# KeyInput.net
KiCad netlist of a schematic drawn in Altium Designer
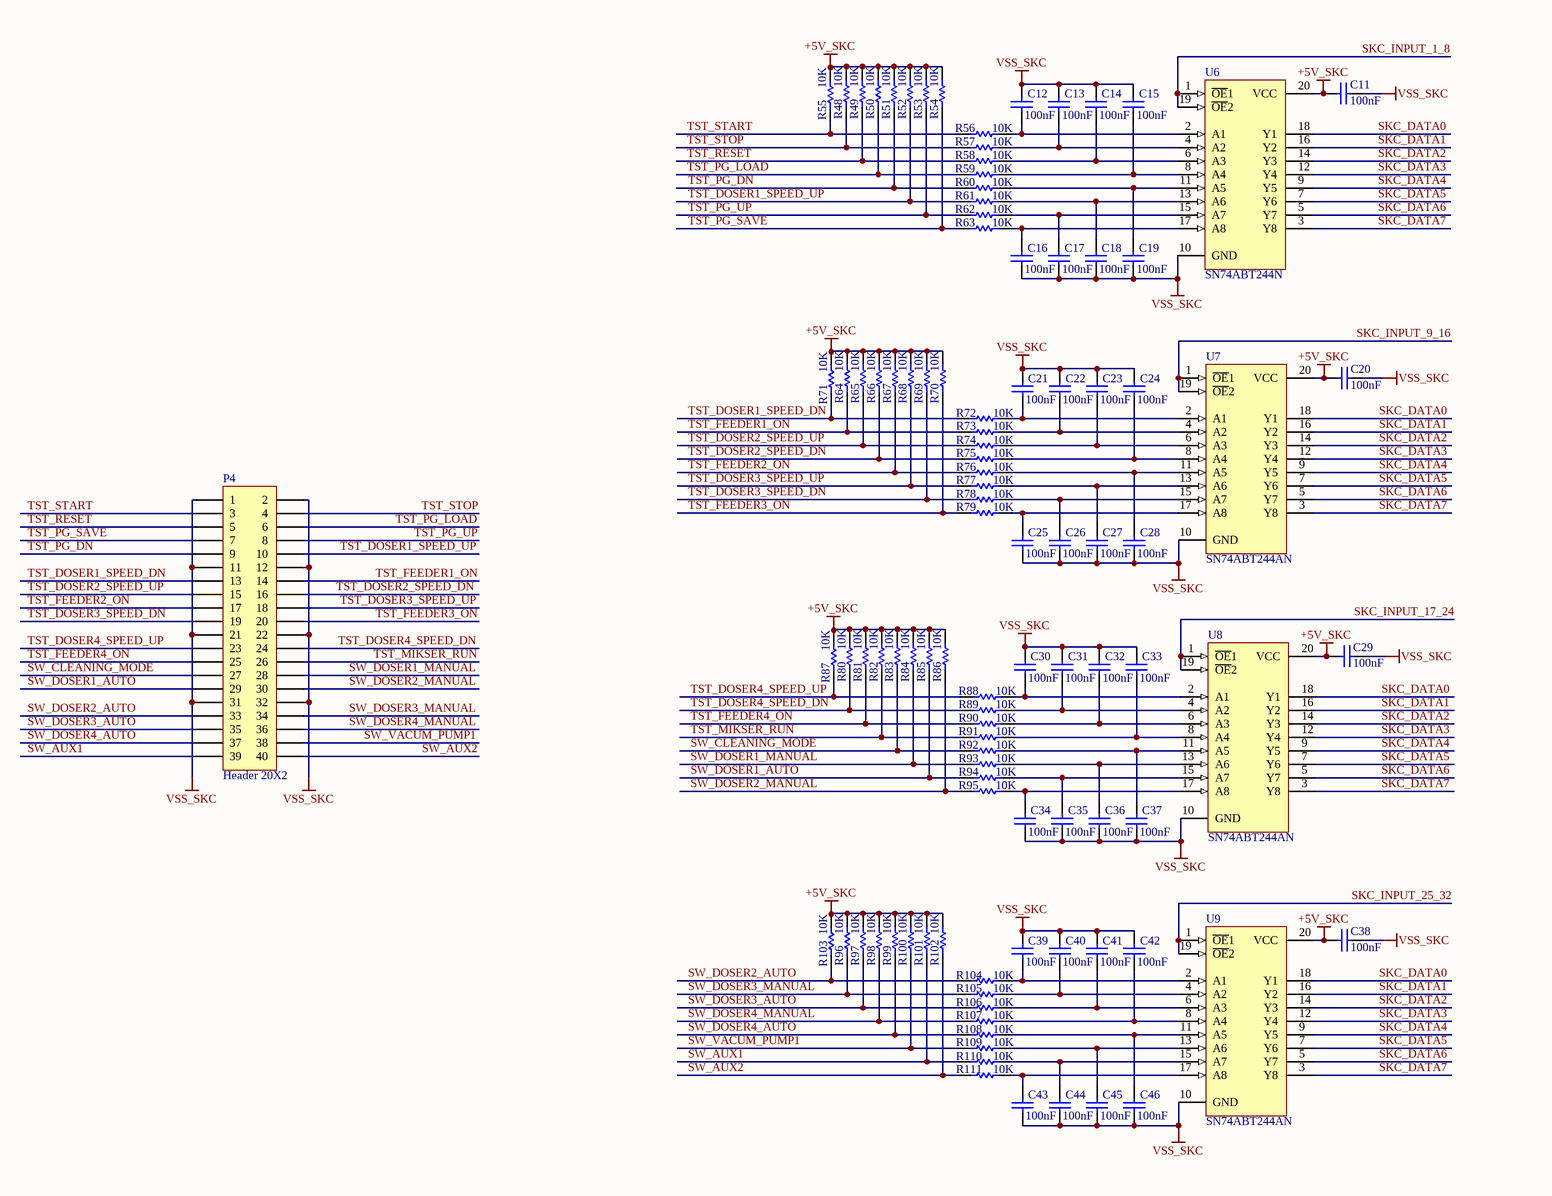
[diagram p0: KeyInput.SchDoc]

(export (version "E")
  (design (tool "Eeschema 10.0.6"))
  (components
    (comp (ref "C11")
      (value "100nF")
      (footprint "1206")
      (description "Ceramic Chip Capacitor - Standard")
      (fields (field (name "PUBLISHER") "Altium Limited"))
      (libsource (lib "KEMET Chip Capacitor") (part "C1206"))
    )
    (comp (ref "C12")
      (value "100nF")
      (footprint "1206")
      (description "Ceramic Chip Capacitor - Standard")
      (fields (field (name "PUBLISHER") "Altium Limited"))
      (libsource (lib "KEMET Chip Capacitor") (part "C1206"))
    )
    (comp (ref "C13")
      (value "100nF")
      (footprint "1206")
      (description "Ceramic Chip Capacitor - Standard")
      (fields (field (name "PUBLISHER") "Altium Limited"))
      (libsource (lib "KEMET Chip Capacitor") (part "C1206"))
    )
    (comp (ref "C14")
      (value "100nF")
      (footprint "1206")
      (description "Ceramic Chip Capacitor - Standard")
      (fields (field (name "PUBLISHER") "Altium Limited"))
      (libsource (lib "KEMET Chip Capacitor") (part "C1206"))
    )
    (comp (ref "C15")
      (value "100nF")
      (footprint "1206")
      (description "Ceramic Chip Capacitor - Standard")
      (fields (field (name "PUBLISHER") "Altium Limited"))
      (libsource (lib "KEMET Chip Capacitor") (part "C1206"))
    )
    (comp (ref "C16")
      (value "100nF")
      (footprint "1206")
      (description "Ceramic Chip Capacitor - Standard")
      (fields (field (name "PUBLISHER") "Altium Limited"))
      (libsource (lib "KEMET Chip Capacitor") (part "C1206"))
    )
    (comp (ref "C17")
      (value "100nF")
      (footprint "1206")
      (description "Ceramic Chip Capacitor - Standard")
      (fields (field (name "PUBLISHER") "Altium Limited"))
      (libsource (lib "KEMET Chip Capacitor") (part "C1206"))
    )
    (comp (ref "C18")
      (value "100nF")
      (footprint "1206")
      (description "Ceramic Chip Capacitor - Standard")
      (fields (field (name "PUBLISHER") "Altium Limited"))
      (libsource (lib "KEMET Chip Capacitor") (part "C1206"))
    )
    (comp (ref "C19")
      (value "100nF")
      (footprint "1206")
      (description "Ceramic Chip Capacitor - Standard")
      (fields (field (name "PUBLISHER") "Altium Limited"))
      (libsource (lib "KEMET Chip Capacitor") (part "C1206"))
    )
    (comp (ref "C20")
      (value "100nF")
      (footprint "1206")
      (description "Ceramic Chip Capacitor - Standard")
      (fields (field (name "PUBLISHER") "Altium Limited"))
      (libsource (lib "KEMET Chip Capacitor") (part "C1206"))
    )
    (comp (ref "C21")
      (value "100nF")
      (footprint "1206")
      (description "Ceramic Chip Capacitor - Standard")
      (fields (field (name "PUBLISHER") "Altium Limited"))
      (libsource (lib "KEMET Chip Capacitor") (part "C1206"))
    )
    (comp (ref "C22")
      (value "100nF")
      (footprint "1206")
      (description "Ceramic Chip Capacitor - Standard")
      (fields (field (name "PUBLISHER") "Altium Limited"))
      (libsource (lib "KEMET Chip Capacitor") (part "C1206"))
    )
    (comp (ref "C23")
      (value "100nF")
      (footprint "1206")
      (description "Ceramic Chip Capacitor - Standard")
      (fields (field (name "PUBLISHER") "Altium Limited"))
      (libsource (lib "KEMET Chip Capacitor") (part "C1206"))
    )
    (comp (ref "C24")
      (value "100nF")
      (footprint "1206")
      (description "Ceramic Chip Capacitor - Standard")
      (fields (field (name "PUBLISHER") "Altium Limited"))
      (libsource (lib "KEMET Chip Capacitor") (part "C1206"))
    )
    (comp (ref "C25")
      (value "100nF")
      (footprint "1206")
      (description "Ceramic Chip Capacitor - Standard")
      (fields (field (name "PUBLISHER") "Altium Limited"))
      (libsource (lib "KEMET Chip Capacitor") (part "C1206"))
    )
    (comp (ref "C26")
      (value "100nF")
      (footprint "1206")
      (description "Ceramic Chip Capacitor - Standard")
      (fields (field (name "PUBLISHER") "Altium Limited"))
      (libsource (lib "KEMET Chip Capacitor") (part "C1206"))
    )
    (comp (ref "C27")
      (value "100nF")
      (footprint "1206")
      (description "Ceramic Chip Capacitor - Standard")
      (fields (field (name "PUBLISHER") "Altium Limited"))
      (libsource (lib "KEMET Chip Capacitor") (part "C1206"))
    )
    (comp (ref "C28")
      (value "100nF")
      (footprint "1206")
      (description "Ceramic Chip Capacitor - Standard")
      (fields (field (name "PUBLISHER") "Altium Limited"))
      (libsource (lib "KEMET Chip Capacitor") (part "C1206"))
    )
    (comp (ref "C29")
      (value "100nF")
      (footprint "1206")
      (description "Ceramic Chip Capacitor - Standard")
      (fields (field (name "PUBLISHER") "Altium Limited"))
      (libsource (lib "KEMET Chip Capacitor") (part "C1206"))
    )
    (comp (ref "C30")
      (value "100nF")
      (footprint "1206")
      (description "Ceramic Chip Capacitor - Standard")
      (fields (field (name "PUBLISHER") "Altium Limited"))
      (libsource (lib "KEMET Chip Capacitor") (part "C1206"))
    )
    (comp (ref "C31")
      (value "100nF")
      (footprint "1206")
      (description "Ceramic Chip Capacitor - Standard")
      (fields (field (name "PUBLISHER") "Altium Limited"))
      (libsource (lib "KEMET Chip Capacitor") (part "C1206"))
    )
    (comp (ref "C32")
      (value "100nF")
      (footprint "1206")
      (description "Ceramic Chip Capacitor - Standard")
      (fields (field (name "PUBLISHER") "Altium Limited"))
      (libsource (lib "KEMET Chip Capacitor") (part "C1206"))
    )
    (comp (ref "C33")
      (value "100nF")
      (footprint "1206")
      (description "Ceramic Chip Capacitor - Standard")
      (fields (field (name "PUBLISHER") "Altium Limited"))
      (libsource (lib "KEMET Chip Capacitor") (part "C1206"))
    )
    (comp (ref "C34")
      (value "100nF")
      (footprint "1206")
      (description "Ceramic Chip Capacitor - Standard")
      (fields (field (name "PUBLISHER") "Altium Limited"))
      (libsource (lib "KEMET Chip Capacitor") (part "C1206"))
    )
    (comp (ref "C35")
      (value "100nF")
      (footprint "1206")
      (description "Ceramic Chip Capacitor - Standard")
      (fields (field (name "PUBLISHER") "Altium Limited"))
      (libsource (lib "KEMET Chip Capacitor") (part "C1206"))
    )
    (comp (ref "C36")
      (value "100nF")
      (footprint "1206")
      (description "Ceramic Chip Capacitor - Standard")
      (fields (field (name "PUBLISHER") "Altium Limited"))
      (libsource (lib "KEMET Chip Capacitor") (part "C1206"))
    )
    (comp (ref "C37")
      (value "100nF")
      (footprint "1206")
      (description "Ceramic Chip Capacitor - Standard")
      (fields (field (name "PUBLISHER") "Altium Limited"))
      (libsource (lib "KEMET Chip Capacitor") (part "C1206"))
    )
    (comp (ref "C38")
      (value "100nF")
      (footprint "1206")
      (description "Ceramic Chip Capacitor - Standard")
      (fields (field (name "PUBLISHER") "Altium Limited"))
      (libsource (lib "KEMET Chip Capacitor") (part "C1206"))
    )
    (comp (ref "C39")
      (value "100nF")
      (footprint "1206")
      (description "Ceramic Chip Capacitor - Standard")
      (fields (field (name "PUBLISHER") "Altium Limited"))
      (libsource (lib "KEMET Chip Capacitor") (part "C1206"))
    )
    (comp (ref "C40")
      (value "100nF")
      (footprint "1206")
      (description "Ceramic Chip Capacitor - Standard")
      (fields (field (name "PUBLISHER") "Altium Limited"))
      (libsource (lib "KEMET Chip Capacitor") (part "C1206"))
    )
    (comp (ref "C41")
      (value "100nF")
      (footprint "1206")
      (description "Ceramic Chip Capacitor - Standard")
      (fields (field (name "PUBLISHER") "Altium Limited"))
      (libsource (lib "KEMET Chip Capacitor") (part "C1206"))
    )
    (comp (ref "C42")
      (value "100nF")
      (footprint "1206")
      (description "Ceramic Chip Capacitor - Standard")
      (fields (field (name "PUBLISHER") "Altium Limited"))
      (libsource (lib "KEMET Chip Capacitor") (part "C1206"))
    )
    (comp (ref "C43")
      (value "100nF")
      (footprint "1206")
      (description "Ceramic Chip Capacitor - Standard")
      (fields (field (name "PUBLISHER") "Altium Limited"))
      (libsource (lib "KEMET Chip Capacitor") (part "C1206"))
    )
    (comp (ref "C44")
      (value "100nF")
      (footprint "1206")
      (description "Ceramic Chip Capacitor - Standard")
      (fields (field (name "PUBLISHER") "Altium Limited"))
      (libsource (lib "KEMET Chip Capacitor") (part "C1206"))
    )
    (comp (ref "C45")
      (value "100nF")
      (footprint "1206")
      (description "Ceramic Chip Capacitor - Standard")
      (fields (field (name "PUBLISHER") "Altium Limited"))
      (libsource (lib "KEMET Chip Capacitor") (part "C1206"))
    )
    (comp (ref "C46")
      (value "100nF")
      (footprint "1206")
      (description "Ceramic Chip Capacitor - Standard")
      (fields (field (name "PUBLISHER") "Altium Limited"))
      (libsource (lib "KEMET Chip Capacitor") (part "C1206"))
    )
    (comp (ref "P4")
      (value "Header 20X2")
      (footprint "HDR2X20")
      (description "Header, 20-Pin, Dual row")
      (fields (field (name "PUBLISHER") "Altium Limited"))
      (libsource (lib "Miscellaneous Connectors") (part "Header 20X2"))
    )
    (comp (ref "R48")
      (value "10K")
      (footprint "ERA-0805")
      (fields (field (name "PUBLISHER") "Altium Limited"))
      (libsource (lib "Panasonic Resistor") (part "ERA6Y"))
    )
    (comp (ref "R49")
      (value "10K")
      (footprint "ERA-0805")
      (fields (field (name "PUBLISHER") "Altium Limited"))
      (libsource (lib "Panasonic Resistor") (part "ERA6Y"))
    )
    (comp (ref "R50")
      (value "10K")
      (footprint "ERA-0805")
      (fields (field (name "PUBLISHER") "Altium Limited"))
      (libsource (lib "Panasonic Resistor") (part "ERA6Y"))
    )
    (comp (ref "R51")
      (value "10K")
      (footprint "ERA-0805")
      (fields (field (name "PUBLISHER") "Altium Limited"))
      (libsource (lib "Panasonic Resistor") (part "ERA6Y"))
    )
    (comp (ref "R52")
      (value "10K")
      (footprint "ERA-0805")
      (fields (field (name "PUBLISHER") "Altium Limited"))
      (libsource (lib "Panasonic Resistor") (part "ERA6Y"))
    )
    (comp (ref "R53")
      (value "10K")
      (footprint "ERA-0805")
      (fields (field (name "PUBLISHER") "Altium Limited"))
      (libsource (lib "Panasonic Resistor") (part "ERA6Y"))
    )
    (comp (ref "R54")
      (value "10K")
      (footprint "ERA-0805")
      (fields (field (name "PUBLISHER") "Altium Limited"))
      (libsource (lib "Panasonic Resistor") (part "ERA6Y"))
    )
    (comp (ref "R55")
      (value "10K")
      (footprint "ERA-0805")
      (fields (field (name "PUBLISHER") "Altium Limited"))
      (libsource (lib "Panasonic Resistor") (part "ERA6Y"))
    )
    (comp (ref "R56")
      (value "10K")
      (footprint "ERA-0805")
      (fields (field (name "PUBLISHER") "Altium Limited"))
      (libsource (lib "Panasonic Resistor") (part "ERA6Y"))
    )
    (comp (ref "R57")
      (value "10K")
      (footprint "ERA-0805")
      (fields (field (name "PUBLISHER") "Altium Limited"))
      (libsource (lib "Panasonic Resistor") (part "ERA6Y"))
    )
    (comp (ref "R58")
      (value "10K")
      (footprint "ERA-0805")
      (fields (field (name "PUBLISHER") "Altium Limited"))
      (libsource (lib "Panasonic Resistor") (part "ERA6Y"))
    )
    (comp (ref "R59")
      (value "10K")
      (footprint "ERA-0805")
      (fields (field (name "PUBLISHER") "Altium Limited"))
      (libsource (lib "Panasonic Resistor") (part "ERA6Y"))
    )
    (comp (ref "R60")
      (value "10K")
      (footprint "ERA-0805")
      (fields (field (name "PUBLISHER") "Altium Limited"))
      (libsource (lib "Panasonic Resistor") (part "ERA6Y"))
    )
    (comp (ref "R61")
      (value "10K")
      (footprint "ERA-0805")
      (fields (field (name "PUBLISHER") "Altium Limited"))
      (libsource (lib "Panasonic Resistor") (part "ERA6Y"))
    )
    (comp (ref "R62")
      (value "10K")
      (footprint "ERA-0805")
      (fields (field (name "PUBLISHER") "Altium Limited"))
      (libsource (lib "Panasonic Resistor") (part "ERA6Y"))
    )
    (comp (ref "R63")
      (value "10K")
      (footprint "ERA-0805")
      (fields (field (name "PUBLISHER") "Altium Limited"))
      (libsource (lib "Panasonic Resistor") (part "ERA6Y"))
    )
    (comp (ref "R64")
      (value "10K")
      (footprint "ERA-0805")
      (fields (field (name "PUBLISHER") "Altium Limited"))
      (libsource (lib "Panasonic Resistor") (part "ERA6Y"))
    )
    (comp (ref "R65")
      (value "10K")
      (footprint "ERA-0805")
      (fields (field (name "PUBLISHER") "Altium Limited"))
      (libsource (lib "Panasonic Resistor") (part "ERA6Y"))
    )
    (comp (ref "R66")
      (value "10K")
      (footprint "ERA-0805")
      (fields (field (name "PUBLISHER") "Altium Limited"))
      (libsource (lib "Panasonic Resistor") (part "ERA6Y"))
    )
    (comp (ref "R67")
      (value "10K")
      (footprint "ERA-0805")
      (fields (field (name "PUBLISHER") "Altium Limited"))
      (libsource (lib "Panasonic Resistor") (part "ERA6Y"))
    )
    (comp (ref "R68")
      (value "10K")
      (footprint "ERA-0805")
      (fields (field (name "PUBLISHER") "Altium Limited"))
      (libsource (lib "Panasonic Resistor") (part "ERA6Y"))
    )
    (comp (ref "R69")
      (value "10K")
      (footprint "ERA-0805")
      (fields (field (name "PUBLISHER") "Altium Limited"))
      (libsource (lib "Panasonic Resistor") (part "ERA6Y"))
    )
    (comp (ref "R70")
      (value "10K")
      (footprint "ERA-0805")
      (fields (field (name "PUBLISHER") "Altium Limited"))
      (libsource (lib "Panasonic Resistor") (part "ERA6Y"))
    )
    (comp (ref "R71")
      (value "10K")
      (footprint "ERA-0805")
      (fields (field (name "PUBLISHER") "Altium Limited"))
      (libsource (lib "Panasonic Resistor") (part "ERA6Y"))
    )
    (comp (ref "R72")
      (value "10K")
      (footprint "ERA-0805")
      (fields (field (name "PUBLISHER") "Altium Limited"))
      (libsource (lib "Panasonic Resistor") (part "ERA6Y"))
    )
    (comp (ref "R73")
      (value "10K")
      (footprint "ERA-0805")
      (fields (field (name "PUBLISHER") "Altium Limited"))
      (libsource (lib "Panasonic Resistor") (part "ERA6Y"))
    )
    (comp (ref "R74")
      (value "10K")
      (footprint "ERA-0805")
      (fields (field (name "PUBLISHER") "Altium Limited"))
      (libsource (lib "Panasonic Resistor") (part "ERA6Y"))
    )
    (comp (ref "R75")
      (value "10K")
      (footprint "ERA-0805")
      (fields (field (name "PUBLISHER") "Altium Limited"))
      (libsource (lib "Panasonic Resistor") (part "ERA6Y"))
    )
    (comp (ref "R76")
      (value "10K")
      (footprint "ERA-0805")
      (fields (field (name "PUBLISHER") "Altium Limited"))
      (libsource (lib "Panasonic Resistor") (part "ERA6Y"))
    )
    (comp (ref "R77")
      (value "10K")
      (footprint "ERA-0805")
      (fields (field (name "PUBLISHER") "Altium Limited"))
      (libsource (lib "Panasonic Resistor") (part "ERA6Y"))
    )
    (comp (ref "R78")
      (value "10K")
      (footprint "ERA-0805")
      (fields (field (name "PUBLISHER") "Altium Limited"))
      (libsource (lib "Panasonic Resistor") (part "ERA6Y"))
    )
    (comp (ref "R79")
      (value "10K")
      (footprint "ERA-0805")
      (fields (field (name "PUBLISHER") "Altium Limited"))
      (libsource (lib "Panasonic Resistor") (part "ERA6Y"))
    )
    (comp (ref "R80")
      (value "10K")
      (footprint "ERA-0805")
      (fields (field (name "PUBLISHER") "Altium Limited"))
      (libsource (lib "Panasonic Resistor") (part "ERA6Y"))
    )
    (comp (ref "R81")
      (value "10K")
      (footprint "ERA-0805")
      (fields (field (name "PUBLISHER") "Altium Limited"))
      (libsource (lib "Panasonic Resistor") (part "ERA6Y"))
    )
    (comp (ref "R82")
      (value "10K")
      (footprint "ERA-0805")
      (fields (field (name "PUBLISHER") "Altium Limited"))
      (libsource (lib "Panasonic Resistor") (part "ERA6Y"))
    )
    (comp (ref "R83")
      (value "10K")
      (footprint "ERA-0805")
      (fields (field (name "PUBLISHER") "Altium Limited"))
      (libsource (lib "Panasonic Resistor") (part "ERA6Y"))
    )
    (comp (ref "R84")
      (value "10K")
      (footprint "ERA-0805")
      (fields (field (name "PUBLISHER") "Altium Limited"))
      (libsource (lib "Panasonic Resistor") (part "ERA6Y"))
    )
    (comp (ref "R85")
      (value "10K")
      (footprint "ERA-0805")
      (fields (field (name "PUBLISHER") "Altium Limited"))
      (libsource (lib "Panasonic Resistor") (part "ERA6Y"))
    )
    (comp (ref "R86")
      (value "10K")
      (footprint "ERA-0805")
      (fields (field (name "PUBLISHER") "Altium Limited"))
      (libsource (lib "Panasonic Resistor") (part "ERA6Y"))
    )
    (comp (ref "R87")
      (value "10K")
      (footprint "ERA-0805")
      (fields (field (name "PUBLISHER") "Altium Limited"))
      (libsource (lib "Panasonic Resistor") (part "ERA6Y"))
    )
    (comp (ref "R88")
      (value "10K")
      (footprint "ERA-0805")
      (fields (field (name "PUBLISHER") "Altium Limited"))
      (libsource (lib "Panasonic Resistor") (part "ERA6Y"))
    )
    (comp (ref "R89")
      (value "10K")
      (footprint "ERA-0805")
      (fields (field (name "PUBLISHER") "Altium Limited"))
      (libsource (lib "Panasonic Resistor") (part "ERA6Y"))
    )
    (comp (ref "R90")
      (value "10K")
      (footprint "ERA-0805")
      (fields (field (name "PUBLISHER") "Altium Limited"))
      (libsource (lib "Panasonic Resistor") (part "ERA6Y"))
    )
    (comp (ref "R91")
      (value "10K")
      (footprint "ERA-0805")
      (fields (field (name "PUBLISHER") "Altium Limited"))
      (libsource (lib "Panasonic Resistor") (part "ERA6Y"))
    )
    (comp (ref "R92")
      (value "10K")
      (footprint "ERA-0805")
      (fields (field (name "PUBLISHER") "Altium Limited"))
      (libsource (lib "Panasonic Resistor") (part "ERA6Y"))
    )
    (comp (ref "R93")
      (value "10K")
      (footprint "ERA-0805")
      (fields (field (name "PUBLISHER") "Altium Limited"))
      (libsource (lib "Panasonic Resistor") (part "ERA6Y"))
    )
    (comp (ref "R94")
      (value "10K")
      (footprint "ERA-0805")
      (fields (field (name "PUBLISHER") "Altium Limited"))
      (libsource (lib "Panasonic Resistor") (part "ERA6Y"))
    )
    (comp (ref "R95")
      (value "10K")
      (footprint "ERA-0805")
      (fields (field (name "PUBLISHER") "Altium Limited"))
      (libsource (lib "Panasonic Resistor") (part "ERA6Y"))
    )
    (comp (ref "R96")
      (value "10K")
      (footprint "ERA-0805")
      (fields (field (name "PUBLISHER") "Altium Limited"))
      (libsource (lib "Panasonic Resistor") (part "ERA6Y"))
    )
    (comp (ref "R97")
      (value "10K")
      (footprint "ERA-0805")
      (fields (field (name "PUBLISHER") "Altium Limited"))
      (libsource (lib "Panasonic Resistor") (part "ERA6Y"))
    )
    (comp (ref "R98")
      (value "10K")
      (footprint "ERA-0805")
      (fields (field (name "PUBLISHER") "Altium Limited"))
      (libsource (lib "Panasonic Resistor") (part "ERA6Y"))
    )
    (comp (ref "R99")
      (value "10K")
      (footprint "ERA-0805")
      (fields (field (name "PUBLISHER") "Altium Limited"))
      (libsource (lib "Panasonic Resistor") (part "ERA6Y"))
    )
    (comp (ref "R100")
      (value "10K")
      (footprint "ERA-0805")
      (fields (field (name "PUBLISHER") "Altium Limited"))
      (libsource (lib "Panasonic Resistor") (part "ERA6Y"))
    )
    (comp (ref "R101")
      (value "10K")
      (footprint "ERA-0805")
      (fields (field (name "PUBLISHER") "Altium Limited"))
      (libsource (lib "Panasonic Resistor") (part "ERA6Y"))
    )
    (comp (ref "R102")
      (value "10K")
      (footprint "ERA-0805")
      (fields (field (name "PUBLISHER") "Altium Limited"))
      (libsource (lib "Panasonic Resistor") (part "ERA6Y"))
    )
    (comp (ref "R103")
      (value "10K")
      (footprint "ERA-0805")
      (fields (field (name "PUBLISHER") "Altium Limited"))
      (libsource (lib "Panasonic Resistor") (part "ERA6Y"))
    )
    (comp (ref "R104")
      (value "10K")
      (footprint "ERA-0805")
      (fields (field (name "PUBLISHER") "Altium Limited"))
      (libsource (lib "Panasonic Resistor") (part "ERA6Y"))
    )
    (comp (ref "R105")
      (value "10K")
      (footprint "ERA-0805")
      (fields (field (name "PUBLISHER") "Altium Limited"))
      (libsource (lib "Panasonic Resistor") (part "ERA6Y"))
    )
    (comp (ref "R106")
      (value "10K")
      (footprint "ERA-0805")
      (fields (field (name "PUBLISHER") "Altium Limited"))
      (libsource (lib "Panasonic Resistor") (part "ERA6Y"))
    )
    (comp (ref "R107")
      (value "10K")
      (footprint "ERA-0805")
      (fields (field (name "PUBLISHER") "Altium Limited"))
      (libsource (lib "Panasonic Resistor") (part "ERA6Y"))
    )
    (comp (ref "R108")
      (value "10K")
      (footprint "ERA-0805")
      (fields (field (name "PUBLISHER") "Altium Limited"))
      (libsource (lib "Panasonic Resistor") (part "ERA6Y"))
    )
    (comp (ref "R109")
      (value "10K")
      (footprint "ERA-0805")
      (fields (field (name "PUBLISHER") "Altium Limited"))
      (libsource (lib "Panasonic Resistor") (part "ERA6Y"))
    )
    (comp (ref "R110")
      (value "10K")
      (footprint "ERA-0805")
      (fields (field (name "PUBLISHER") "Altium Limited"))
      (libsource (lib "Panasonic Resistor") (part "ERA6Y"))
    )
    (comp (ref "R111")
      (value "10K")
      (footprint "ERA-0805")
      (fields (field (name "PUBLISHER") "Altium Limited"))
      (libsource (lib "Panasonic Resistor") (part "ERA6Y"))
    )
    (comp (ref "U6")
      (value "SN74ABT244N")
      (footprint "N020")
      (description "Octal Buffer/Driver with 3-State Outputs")
      (fields (field (name "PUBLISHER") "Altium Limited"))
      (libsource (lib "TI Logic Buffer Line Driver") (part "SN74ABT244N"))
    )
    (comp (ref "U7")
      (value "SN74ABT244AN")
      (footprint "N020")
      (description "Octal Buffer/Driver with 3-State Outputs")
      (fields (field (name "PUBLISHER") "Altium Limited"))
      (libsource (lib "TI Logic Buffer Line Driver") (part "SN74ABT244AN"))
    )
    (comp (ref "U8")
      (value "SN74ABT244AN")
      (footprint "N020")
      (description "Octal Buffer/Driver with 3-State Outputs")
      (fields (field (name "PUBLISHER") "Altium Limited"))
      (libsource (lib "TI Logic Buffer Line Driver") (part "SN74ABT244AN"))
    )
    (comp (ref "U9")
      (value "SN74ABT244AN")
      (footprint "N020")
      (description "Octal Buffer/Driver with 3-State Outputs")
      (fields (field (name "PUBLISHER") "Altium Limited"))
      (libsource (lib "TI Logic Buffer Line Driver") (part "SN74ABT244AN"))
    )
  )
  (nets
    (net (code "1") (name "+5V_SKC") (class "Default")
      (node (ref "C11") (pin "1") (pinfunction "1_1") (pintype "passive"))
      (node (ref "C20") (pin "1") (pinfunction "1_1") (pintype "passive"))
      (node (ref "C29") (pin "1") (pinfunction "1_1") (pintype "passive"))
      (node (ref "C38") (pin "1") (pinfunction "1_1") (pintype "passive"))
      (node (ref "R100") (pin "2") (pinfunction "2_2") (pintype "passive"))
      (node (ref "R101") (pin "2") (pinfunction "2_2") (pintype "passive"))
      (node (ref "R102") (pin "2") (pinfunction "2_2") (pintype "passive"))
      (node (ref "R103") (pin "2") (pinfunction "2_2") (pintype "passive"))
      (node (ref "R48") (pin "2") (pinfunction "2_2") (pintype "passive"))
      (node (ref "R49") (pin "2") (pinfunction "2_2") (pintype "passive"))
      (node (ref "R50") (pin "2") (pinfunction "2_2") (pintype "passive"))
      (node (ref "R51") (pin "2") (pinfunction "2_2") (pintype "passive"))
      (node (ref "R52") (pin "2") (pinfunction "2_2") (pintype "passive"))
      (node (ref "R53") (pin "2") (pinfunction "2_2") (pintype "passive"))
      (node (ref "R54") (pin "2") (pinfunction "2_2") (pintype "passive"))
      (node (ref "R55") (pin "2") (pinfunction "2_2") (pintype "passive"))
      (node (ref "R64") (pin "2") (pinfunction "2_2") (pintype "passive"))
      (node (ref "R65") (pin "2") (pinfunction "2_2") (pintype "passive"))
      (node (ref "R66") (pin "2") (pinfunction "2_2") (pintype "passive"))
      (node (ref "R67") (pin "2") (pinfunction "2_2") (pintype "passive"))
      (node (ref "R68") (pin "2") (pinfunction "2_2") (pintype "passive"))
      (node (ref "R69") (pin "2") (pinfunction "2_2") (pintype "passive"))
      (node (ref "R70") (pin "2") (pinfunction "2_2") (pintype "passive"))
      (node (ref "R71") (pin "2") (pinfunction "2_2") (pintype "passive"))
      (node (ref "R80") (pin "2") (pinfunction "2_2") (pintype "passive"))
      (node (ref "R81") (pin "2") (pinfunction "2_2") (pintype "passive"))
      (node (ref "R82") (pin "2") (pinfunction "2_2") (pintype "passive"))
      (node (ref "R83") (pin "2") (pinfunction "2_2") (pintype "passive"))
      (node (ref "R84") (pin "2") (pinfunction "2_2") (pintype "passive"))
      (node (ref "R85") (pin "2") (pinfunction "2_2") (pintype "passive"))
      (node (ref "R86") (pin "2") (pinfunction "2_2") (pintype "passive"))
      (node (ref "R87") (pin "2") (pinfunction "2_2") (pintype "passive"))
      (node (ref "R96") (pin "2") (pinfunction "2_2") (pintype "passive"))
      (node (ref "R97") (pin "2") (pinfunction "2_2") (pintype "passive"))
      (node (ref "R98") (pin "2") (pinfunction "2_2") (pintype "passive"))
      (node (ref "R99") (pin "2") (pinfunction "2_2") (pintype "passive"))
      (node (ref "U6") (pin "20") (pinfunction "VCC_20") (pintype "power_in"))
      (node (ref "U7") (pin "20") (pinfunction "VCC_20") (pintype "power_in"))
      (node (ref "U8") (pin "20") (pinfunction "VCC_20") (pintype "power_in"))
      (node (ref "U9") (pin "20") (pinfunction "VCC_20") (pintype "power_in"))
    )
    (net (code "2") (name "/SKC_DATA0") (class "Default")
      (node (ref "U6") (pin "18") (pinfunction "Y1_18") (pintype "tri_state"))
      (node (ref "U7") (pin "18") (pinfunction "Y1_18") (pintype "tri_state"))
      (node (ref "U8") (pin "18") (pinfunction "Y1_18") (pintype "tri_state"))
      (node (ref "U9") (pin "18") (pinfunction "Y1_18") (pintype "tri_state"))
    )
    (net (code "3") (name "/SKC_DATA1") (class "Default")
      (node (ref "U6") (pin "16") (pinfunction "Y2_16") (pintype "tri_state"))
      (node (ref "U7") (pin "16") (pinfunction "Y2_16") (pintype "tri_state"))
      (node (ref "U8") (pin "16") (pinfunction "Y2_16") (pintype "tri_state"))
      (node (ref "U9") (pin "16") (pinfunction "Y2_16") (pintype "tri_state"))
    )
    (net (code "4") (name "/SKC_DATA2") (class "Default")
      (node (ref "U6") (pin "14") (pinfunction "Y3_14") (pintype "tri_state"))
      (node (ref "U7") (pin "14") (pinfunction "Y3_14") (pintype "tri_state"))
      (node (ref "U8") (pin "14") (pinfunction "Y3_14") (pintype "tri_state"))
      (node (ref "U9") (pin "14") (pinfunction "Y3_14") (pintype "tri_state"))
    )
    (net (code "5") (name "/SKC_DATA3") (class "Default")
      (node (ref "U6") (pin "12") (pinfunction "Y4_12") (pintype "tri_state"))
      (node (ref "U7") (pin "12") (pinfunction "Y4_12") (pintype "tri_state"))
      (node (ref "U8") (pin "12") (pinfunction "Y4_12") (pintype "tri_state"))
      (node (ref "U9") (pin "12") (pinfunction "Y4_12") (pintype "tri_state"))
    )
    (net (code "6") (name "/SKC_DATA4") (class "Default")
      (node (ref "U6") (pin "9") (pinfunction "Y5_9") (pintype "tri_state"))
      (node (ref "U7") (pin "9") (pinfunction "Y5_9") (pintype "tri_state"))
      (node (ref "U8") (pin "9") (pinfunction "Y5_9") (pintype "tri_state"))
      (node (ref "U9") (pin "9") (pinfunction "Y5_9") (pintype "tri_state"))
    )
    (net (code "7") (name "/SKC_DATA5") (class "Default")
      (node (ref "U6") (pin "7") (pinfunction "Y6_7") (pintype "tri_state"))
      (node (ref "U7") (pin "7") (pinfunction "Y6_7") (pintype "tri_state"))
      (node (ref "U8") (pin "7") (pinfunction "Y6_7") (pintype "tri_state"))
      (node (ref "U9") (pin "7") (pinfunction "Y6_7") (pintype "tri_state"))
    )
    (net (code "8") (name "/SKC_DATA6") (class "Default")
      (node (ref "U6") (pin "5") (pinfunction "Y7_5") (pintype "tri_state"))
      (node (ref "U7") (pin "5") (pinfunction "Y7_5") (pintype "tri_state"))
      (node (ref "U8") (pin "5") (pinfunction "Y7_5") (pintype "tri_state"))
      (node (ref "U9") (pin "5") (pinfunction "Y7_5") (pintype "tri_state"))
    )
    (net (code "9") (name "/SKC_DATA7") (class "Default")
      (node (ref "U6") (pin "3") (pinfunction "Y8_3") (pintype "tri_state"))
      (node (ref "U7") (pin "3") (pinfunction "Y8_3") (pintype "tri_state"))
      (node (ref "U8") (pin "3") (pinfunction "Y8_3") (pintype "tri_state"))
      (node (ref "U9") (pin "3") (pinfunction "Y8_3") (pintype "tri_state"))
    )
    (net (code "10") (name "/SKC_INPUT_1_8") (class "Default")
      (node (ref "U6") (pin "1") (pinfunction "~{OE}1_1") (pintype "input"))
      (node (ref "U6") (pin "19") (pinfunction "~{OE}2_19") (pintype "input"))
    )
    (net (code "11") (name "/SKC_INPUT_9_16") (class "Default")
      (node (ref "U7") (pin "1") (pinfunction "~{OE}1_1") (pintype "input"))
      (node (ref "U7") (pin "19") (pinfunction "~{OE}2_19") (pintype "input"))
    )
    (net (code "12") (name "/SKC_INPUT_17_24") (class "Default")
      (node (ref "U8") (pin "1") (pinfunction "~{OE}1_1") (pintype "input"))
      (node (ref "U8") (pin "19") (pinfunction "~{OE}2_19") (pintype "input"))
    )
    (net (code "13") (name "/SKC_INPUT_25_32") (class "Default")
      (node (ref "U9") (pin "1") (pinfunction "~{OE}1_1") (pintype "input"))
      (node (ref "U9") (pin "19") (pinfunction "~{OE}2_19") (pintype "input"))
    )
    (net (code "14") (name "/SW_AUX1") (class "Default")
      (node (ref "P4") (pin "39") (pinfunction "39_39") (pintype "passive"))
      (node (ref "R101") (pin "1") (pinfunction "1_1") (pintype "passive"))
      (node (ref "R110") (pin "1") (pinfunction "1_1") (pintype "passive"))
    )
    (net (code "15") (name "/SW_AUX2") (class "Default")
      (node (ref "P4") (pin "40") (pinfunction "40_40") (pintype "passive"))
      (node (ref "R102") (pin "1") (pinfunction "1_1") (pintype "passive"))
      (node (ref "R111") (pin "1") (pinfunction "1_1") (pintype "passive"))
    )
    (net (code "16") (name "/SW_CLEANING_MODE") (class "Default")
      (node (ref "P4") (pin "27") (pinfunction "27_27") (pintype "passive"))
      (node (ref "R83") (pin "1") (pinfunction "1_1") (pintype "passive"))
      (node (ref "R92") (pin "1") (pinfunction "1_1") (pintype "passive"))
    )
    (net (code "17") (name "/SW_DOSER1_AUTO") (class "Default")
      (node (ref "P4") (pin "29") (pinfunction "29_29") (pintype "passive"))
      (node (ref "R85") (pin "1") (pinfunction "1_1") (pintype "passive"))
      (node (ref "R94") (pin "1") (pinfunction "1_1") (pintype "passive"))
    )
    (net (code "18") (name "/SW_DOSER1_MANUAL") (class "Default")
      (node (ref "P4") (pin "28") (pinfunction "28_28") (pintype "passive"))
      (node (ref "R84") (pin "1") (pinfunction "1_1") (pintype "passive"))
      (node (ref "R93") (pin "1") (pinfunction "1_1") (pintype "passive"))
    )
    (net (code "19") (name "/SW_DOSER2_AUTO") (class "Default")
      (node (ref "P4") (pin "33") (pinfunction "33_33") (pintype "passive"))
      (node (ref "R103") (pin "1") (pinfunction "1_1") (pintype "passive"))
      (node (ref "R104") (pin "1") (pinfunction "1_1") (pintype "passive"))
    )
    (net (code "20") (name "/SW_DOSER2_MANUAL") (class "Default")
      (node (ref "P4") (pin "30") (pinfunction "30_30") (pintype "passive"))
      (node (ref "R86") (pin "1") (pinfunction "1_1") (pintype "passive"))
      (node (ref "R95") (pin "1") (pinfunction "1_1") (pintype "passive"))
    )
    (net (code "21") (name "/SW_DOSER3_AUTO") (class "Default")
      (node (ref "P4") (pin "35") (pinfunction "35_35") (pintype "passive"))
      (node (ref "R106") (pin "1") (pinfunction "1_1") (pintype "passive"))
      (node (ref "R97") (pin "1") (pinfunction "1_1") (pintype "passive"))
    )
    (net (code "22") (name "/SW_DOSER3_MANUAL") (class "Default")
      (node (ref "P4") (pin "34") (pinfunction "34_34") (pintype "passive"))
      (node (ref "R105") (pin "1") (pinfunction "1_1") (pintype "passive"))
      (node (ref "R96") (pin "1") (pinfunction "1_1") (pintype "passive"))
    )
    (net (code "23") (name "/SW_DOSER4_AUTO") (class "Default")
      (node (ref "P4") (pin "37") (pinfunction "37_37") (pintype "passive"))
      (node (ref "R108") (pin "1") (pinfunction "1_1") (pintype "passive"))
      (node (ref "R99") (pin "1") (pinfunction "1_1") (pintype "passive"))
    )
    (net (code "24") (name "/SW_DOSER4_MANUAL") (class "Default")
      (node (ref "P4") (pin "36") (pinfunction "36_36") (pintype "passive"))
      (node (ref "R107") (pin "1") (pinfunction "1_1") (pintype "passive"))
      (node (ref "R98") (pin "1") (pinfunction "1_1") (pintype "passive"))
    )
    (net (code "25") (name "/SW_VACUM_PUMP1") (class "Default")
      (node (ref "P4") (pin "38") (pinfunction "38_38") (pintype "passive"))
      (node (ref "R100") (pin "1") (pinfunction "1_1") (pintype "passive"))
      (node (ref "R109") (pin "1") (pinfunction "1_1") (pintype "passive"))
    )
    (net (code "26") (name "/TST_DOSER1_SPEED_DN") (class "Default")
      (node (ref "P4") (pin "13") (pinfunction "13_13") (pintype "passive"))
      (node (ref "R71") (pin "1") (pinfunction "1_1") (pintype "passive"))
      (node (ref "R72") (pin "1") (pinfunction "1_1") (pintype "passive"))
    )
    (net (code "27") (name "/TST_DOSER1_SPEED_UP") (class "Default")
      (node (ref "P4") (pin "10") (pinfunction "10_10") (pintype "passive"))
      (node (ref "R52") (pin "1") (pinfunction "1_1") (pintype "passive"))
      (node (ref "R61") (pin "1") (pinfunction "1_1") (pintype "passive"))
    )
    (net (code "28") (name "/TST_DOSER2_SPEED_DN") (class "Default")
      (node (ref "P4") (pin "16") (pinfunction "16_16") (pintype "passive"))
      (node (ref "R66") (pin "1") (pinfunction "1_1") (pintype "passive"))
      (node (ref "R75") (pin "1") (pinfunction "1_1") (pintype "passive"))
    )
    (net (code "29") (name "/TST_DOSER2_SPEED_UP") (class "Default")
      (node (ref "P4") (pin "15") (pinfunction "15_15") (pintype "passive"))
      (node (ref "R65") (pin "1") (pinfunction "1_1") (pintype "passive"))
      (node (ref "R74") (pin "1") (pinfunction "1_1") (pintype "passive"))
    )
    (net (code "30") (name "/TST_DOSER3_SPEED_DN") (class "Default")
      (node (ref "P4") (pin "19") (pinfunction "19_19") (pintype "passive"))
      (node (ref "R69") (pin "1") (pinfunction "1_1") (pintype "passive"))
      (node (ref "R78") (pin "1") (pinfunction "1_1") (pintype "passive"))
    )
    (net (code "31") (name "/TST_DOSER3_SPEED_UP") (class "Default")
      (node (ref "P4") (pin "18") (pinfunction "18_18") (pintype "passive"))
      (node (ref "R68") (pin "1") (pinfunction "1_1") (pintype "passive"))
      (node (ref "R77") (pin "1") (pinfunction "1_1") (pintype "passive"))
    )
    (net (code "32") (name "/TST_DOSER4_SPEED_DN") (class "Default")
      (node (ref "P4") (pin "24") (pinfunction "24_24") (pintype "passive"))
      (node (ref "R80") (pin "1") (pinfunction "1_1") (pintype "passive"))
      (node (ref "R89") (pin "1") (pinfunction "1_1") (pintype "passive"))
    )
    (net (code "33") (name "/TST_DOSER4_SPEED_UP") (class "Default")
      (node (ref "P4") (pin "23") (pinfunction "23_23") (pintype "passive"))
      (node (ref "R87") (pin "1") (pinfunction "1_1") (pintype "passive"))
      (node (ref "R88") (pin "1") (pinfunction "1_1") (pintype "passive"))
    )
    (net (code "34") (name "/TST_FEEDER1_ON") (class "Default")
      (node (ref "P4") (pin "14") (pinfunction "14_14") (pintype "passive"))
      (node (ref "R64") (pin "1") (pinfunction "1_1") (pintype "passive"))
      (node (ref "R73") (pin "1") (pinfunction "1_1") (pintype "passive"))
    )
    (net (code "35") (name "/TST_FEEDER2_ON") (class "Default")
      (node (ref "P4") (pin "17") (pinfunction "17_17") (pintype "passive"))
      (node (ref "R67") (pin "1") (pinfunction "1_1") (pintype "passive"))
      (node (ref "R76") (pin "1") (pinfunction "1_1") (pintype "passive"))
    )
    (net (code "36") (name "/TST_FEEDER3_ON") (class "Default")
      (node (ref "P4") (pin "20") (pinfunction "20_20") (pintype "passive"))
      (node (ref "R70") (pin "1") (pinfunction "1_1") (pintype "passive"))
      (node (ref "R79") (pin "1") (pinfunction "1_1") (pintype "passive"))
    )
    (net (code "37") (name "/TST_FEEDER4_ON") (class "Default")
      (node (ref "P4") (pin "25") (pinfunction "25_25") (pintype "passive"))
      (node (ref "R81") (pin "1") (pinfunction "1_1") (pintype "passive"))
      (node (ref "R90") (pin "1") (pinfunction "1_1") (pintype "passive"))
    )
    (net (code "38") (name "/TST_MIKSER_RUN") (class "Default")
      (node (ref "P4") (pin "26") (pinfunction "26_26") (pintype "passive"))
      (node (ref "R82") (pin "1") (pinfunction "1_1") (pintype "passive"))
      (node (ref "R91") (pin "1") (pinfunction "1_1") (pintype "passive"))
    )
    (net (code "39") (name "/TST_PG_DN") (class "Default")
      (node (ref "P4") (pin "9") (pinfunction "9_9") (pintype "passive"))
      (node (ref "R51") (pin "1") (pinfunction "1_1") (pintype "passive"))
      (node (ref "R60") (pin "1") (pinfunction "1_1") (pintype "passive"))
    )
    (net (code "40") (name "/TST_PG_LOAD") (class "Default")
      (node (ref "P4") (pin "6") (pinfunction "6_6") (pintype "passive"))
      (node (ref "R50") (pin "1") (pinfunction "1_1") (pintype "passive"))
      (node (ref "R59") (pin "1") (pinfunction "1_1") (pintype "passive"))
    )
    (net (code "41") (name "/TST_PG_SAVE") (class "Default")
      (node (ref "P4") (pin "7") (pinfunction "7_7") (pintype "passive"))
      (node (ref "R54") (pin "1") (pinfunction "1_1") (pintype "passive"))
      (node (ref "R63") (pin "1") (pinfunction "1_1") (pintype "passive"))
    )
    (net (code "42") (name "/TST_PG_UP") (class "Default")
      (node (ref "P4") (pin "8") (pinfunction "8_8") (pintype "passive"))
      (node (ref "R53") (pin "1") (pinfunction "1_1") (pintype "passive"))
      (node (ref "R62") (pin "1") (pinfunction "1_1") (pintype "passive"))
    )
    (net (code "43") (name "/TST_RESET") (class "Default")
      (node (ref "P4") (pin "5") (pinfunction "5_5") (pintype "passive"))
      (node (ref "R49") (pin "1") (pinfunction "1_1") (pintype "passive"))
      (node (ref "R58") (pin "1") (pinfunction "1_1") (pintype "passive"))
    )
    (net (code "44") (name "/TST_START") (class "Default")
      (node (ref "P4") (pin "3") (pinfunction "3_3") (pintype "passive"))
      (node (ref "R55") (pin "1") (pinfunction "1_1") (pintype "passive"))
      (node (ref "R56") (pin "1") (pinfunction "1_1") (pintype "passive"))
    )
    (net (code "45") (name "/TST_STOP") (class "Default")
      (node (ref "P4") (pin "4") (pinfunction "4_4") (pintype "passive"))
      (node (ref "R48") (pin "1") (pinfunction "1_1") (pintype "passive"))
      (node (ref "R57") (pin "1") (pinfunction "1_1") (pintype "passive"))
    )
    (net (code "46") (name "Net-(U6-A1)") (class "Default")
      (node (ref "C12") (pin "1") (pinfunction "1_1") (pintype "passive"))
      (node (ref "R56") (pin "2") (pinfunction "2_2") (pintype "passive"))
      (node (ref "U6") (pin "2") (pinfunction "A1_2") (pintype "input"))
    )
    (net (code "47") (name "Net-(U6-A2)") (class "Default")
      (node (ref "C13") (pin "1") (pinfunction "1_1") (pintype "passive"))
      (node (ref "R57") (pin "2") (pinfunction "2_2") (pintype "passive"))
      (node (ref "U6") (pin "4") (pinfunction "A2_4") (pintype "input"))
    )
    (net (code "48") (name "Net-(U6-A3)") (class "Default")
      (node (ref "C14") (pin "1") (pinfunction "1_1") (pintype "passive"))
      (node (ref "R58") (pin "2") (pinfunction "2_2") (pintype "passive"))
      (node (ref "U6") (pin "6") (pinfunction "A3_6") (pintype "input"))
    )
    (net (code "49") (name "Net-(U6-A4)") (class "Default")
      (node (ref "C15") (pin "1") (pinfunction "1_1") (pintype "passive"))
      (node (ref "R59") (pin "2") (pinfunction "2_2") (pintype "passive"))
      (node (ref "U6") (pin "8") (pinfunction "A4_8") (pintype "input"))
    )
    (net (code "50") (name "Net-(U6-A5)") (class "Default")
      (node (ref "C19") (pin "2") (pinfunction "2_2") (pintype "passive"))
      (node (ref "R60") (pin "2") (pinfunction "2_2") (pintype "passive"))
      (node (ref "U6") (pin "11") (pinfunction "A5_11") (pintype "input"))
    )
    (net (code "51") (name "Net-(U6-A6)") (class "Default")
      (node (ref "C18") (pin "2") (pinfunction "2_2") (pintype "passive"))
      (node (ref "R61") (pin "2") (pinfunction "2_2") (pintype "passive"))
      (node (ref "U6") (pin "13") (pinfunction "A6_13") (pintype "input"))
    )
    (net (code "52") (name "Net-(U6-A7)") (class "Default")
      (node (ref "C17") (pin "2") (pinfunction "2_2") (pintype "passive"))
      (node (ref "R62") (pin "2") (pinfunction "2_2") (pintype "passive"))
      (node (ref "U6") (pin "15") (pinfunction "A7_15") (pintype "input"))
    )
    (net (code "53") (name "Net-(U6-A8)") (class "Default")
      (node (ref "C16") (pin "2") (pinfunction "2_2") (pintype "passive"))
      (node (ref "R63") (pin "2") (pinfunction "2_2") (pintype "passive"))
      (node (ref "U6") (pin "17") (pinfunction "A8_17") (pintype "input"))
    )
    (net (code "54") (name "Net-(U7-A1)") (class "Default")
      (node (ref "C21") (pin "1") (pinfunction "1_1") (pintype "passive"))
      (node (ref "R72") (pin "2") (pinfunction "2_2") (pintype "passive"))
      (node (ref "U7") (pin "2") (pinfunction "A1_2") (pintype "input"))
    )
    (net (code "55") (name "Net-(U7-A2)") (class "Default")
      (node (ref "C22") (pin "1") (pinfunction "1_1") (pintype "passive"))
      (node (ref "R73") (pin "2") (pinfunction "2_2") (pintype "passive"))
      (node (ref "U7") (pin "4") (pinfunction "A2_4") (pintype "input"))
    )
    (net (code "56") (name "Net-(U7-A3)") (class "Default")
      (node (ref "C23") (pin "1") (pinfunction "1_1") (pintype "passive"))
      (node (ref "R74") (pin "2") (pinfunction "2_2") (pintype "passive"))
      (node (ref "U7") (pin "6") (pinfunction "A3_6") (pintype "input"))
    )
    (net (code "57") (name "Net-(U7-A4)") (class "Default")
      (node (ref "C24") (pin "1") (pinfunction "1_1") (pintype "passive"))
      (node (ref "R75") (pin "2") (pinfunction "2_2") (pintype "passive"))
      (node (ref "U7") (pin "8") (pinfunction "A4_8") (pintype "input"))
    )
    (net (code "58") (name "Net-(U7-A5)") (class "Default")
      (node (ref "C28") (pin "2") (pinfunction "2_2") (pintype "passive"))
      (node (ref "R76") (pin "2") (pinfunction "2_2") (pintype "passive"))
      (node (ref "U7") (pin "11") (pinfunction "A5_11") (pintype "input"))
    )
    (net (code "59") (name "Net-(U7-A6)") (class "Default")
      (node (ref "C27") (pin "2") (pinfunction "2_2") (pintype "passive"))
      (node (ref "R77") (pin "2") (pinfunction "2_2") (pintype "passive"))
      (node (ref "U7") (pin "13") (pinfunction "A6_13") (pintype "input"))
    )
    (net (code "60") (name "Net-(U7-A7)") (class "Default")
      (node (ref "C26") (pin "2") (pinfunction "2_2") (pintype "passive"))
      (node (ref "R78") (pin "2") (pinfunction "2_2") (pintype "passive"))
      (node (ref "U7") (pin "15") (pinfunction "A7_15") (pintype "input"))
    )
    (net (code "61") (name "Net-(U7-A8)") (class "Default")
      (node (ref "C25") (pin "2") (pinfunction "2_2") (pintype "passive"))
      (node (ref "R79") (pin "2") (pinfunction "2_2") (pintype "passive"))
      (node (ref "U7") (pin "17") (pinfunction "A8_17") (pintype "input"))
    )
    (net (code "62") (name "Net-(U8-A1)") (class "Default")
      (node (ref "C30") (pin "1") (pinfunction "1_1") (pintype "passive"))
      (node (ref "R88") (pin "2") (pinfunction "2_2") (pintype "passive"))
      (node (ref "U8") (pin "2") (pinfunction "A1_2") (pintype "input"))
    )
    (net (code "63") (name "Net-(U8-A2)") (class "Default")
      (node (ref "C31") (pin "1") (pinfunction "1_1") (pintype "passive"))
      (node (ref "R89") (pin "2") (pinfunction "2_2") (pintype "passive"))
      (node (ref "U8") (pin "4") (pinfunction "A2_4") (pintype "input"))
    )
    (net (code "64") (name "Net-(U8-A3)") (class "Default")
      (node (ref "C32") (pin "1") (pinfunction "1_1") (pintype "passive"))
      (node (ref "R90") (pin "2") (pinfunction "2_2") (pintype "passive"))
      (node (ref "U8") (pin "6") (pinfunction "A3_6") (pintype "input"))
    )
    (net (code "65") (name "Net-(U8-A4)") (class "Default")
      (node (ref "C33") (pin "1") (pinfunction "1_1") (pintype "passive"))
      (node (ref "R91") (pin "2") (pinfunction "2_2") (pintype "passive"))
      (node (ref "U8") (pin "8") (pinfunction "A4_8") (pintype "input"))
    )
    (net (code "66") (name "Net-(U8-A5)") (class "Default")
      (node (ref "C37") (pin "2") (pinfunction "2_2") (pintype "passive"))
      (node (ref "R92") (pin "2") (pinfunction "2_2") (pintype "passive"))
      (node (ref "U8") (pin "11") (pinfunction "A5_11") (pintype "input"))
    )
    (net (code "67") (name "Net-(U8-A6)") (class "Default")
      (node (ref "C36") (pin "2") (pinfunction "2_2") (pintype "passive"))
      (node (ref "R93") (pin "2") (pinfunction "2_2") (pintype "passive"))
      (node (ref "U8") (pin "13") (pinfunction "A6_13") (pintype "input"))
    )
    (net (code "68") (name "Net-(U8-A7)") (class "Default")
      (node (ref "C35") (pin "2") (pinfunction "2_2") (pintype "passive"))
      (node (ref "R94") (pin "2") (pinfunction "2_2") (pintype "passive"))
      (node (ref "U8") (pin "15") (pinfunction "A7_15") (pintype "input"))
    )
    (net (code "69") (name "Net-(U8-A8)") (class "Default")
      (node (ref "C34") (pin "2") (pinfunction "2_2") (pintype "passive"))
      (node (ref "R95") (pin "2") (pinfunction "2_2") (pintype "passive"))
      (node (ref "U8") (pin "17") (pinfunction "A8_17") (pintype "input"))
    )
    (net (code "70") (name "Net-(U9-A1)") (class "Default")
      (node (ref "C39") (pin "1") (pinfunction "1_1") (pintype "passive"))
      (node (ref "R104") (pin "2") (pinfunction "2_2") (pintype "passive"))
      (node (ref "U9") (pin "2") (pinfunction "A1_2") (pintype "input"))
    )
    (net (code "71") (name "Net-(U9-A2)") (class "Default")
      (node (ref "C40") (pin "1") (pinfunction "1_1") (pintype "passive"))
      (node (ref "R105") (pin "2") (pinfunction "2_2") (pintype "passive"))
      (node (ref "U9") (pin "4") (pinfunction "A2_4") (pintype "input"))
    )
    (net (code "72") (name "Net-(U9-A3)") (class "Default")
      (node (ref "C41") (pin "1") (pinfunction "1_1") (pintype "passive"))
      (node (ref "R106") (pin "2") (pinfunction "2_2") (pintype "passive"))
      (node (ref "U9") (pin "6") (pinfunction "A3_6") (pintype "input"))
    )
    (net (code "73") (name "Net-(U9-A4)") (class "Default")
      (node (ref "C42") (pin "1") (pinfunction "1_1") (pintype "passive"))
      (node (ref "R107") (pin "2") (pinfunction "2_2") (pintype "passive"))
      (node (ref "U9") (pin "8") (pinfunction "A4_8") (pintype "input"))
    )
    (net (code "74") (name "Net-(U9-A5)") (class "Default")
      (node (ref "C46") (pin "2") (pinfunction "2_2") (pintype "passive"))
      (node (ref "R108") (pin "2") (pinfunction "2_2") (pintype "passive"))
      (node (ref "U9") (pin "11") (pinfunction "A5_11") (pintype "input"))
    )
    (net (code "75") (name "Net-(U9-A6)") (class "Default")
      (node (ref "C45") (pin "2") (pinfunction "2_2") (pintype "passive"))
      (node (ref "R109") (pin "2") (pinfunction "2_2") (pintype "passive"))
      (node (ref "U9") (pin "13") (pinfunction "A6_13") (pintype "input"))
    )
    (net (code "76") (name "Net-(U9-A7)") (class "Default")
      (node (ref "C44") (pin "2") (pinfunction "2_2") (pintype "passive"))
      (node (ref "R110") (pin "2") (pinfunction "2_2") (pintype "passive"))
      (node (ref "U9") (pin "15") (pinfunction "A7_15") (pintype "input"))
    )
    (net (code "77") (name "Net-(U9-A8)") (class "Default")
      (node (ref "C43") (pin "2") (pinfunction "2_2") (pintype "passive"))
      (node (ref "R111") (pin "2") (pinfunction "2_2") (pintype "passive"))
      (node (ref "U9") (pin "17") (pinfunction "A8_17") (pintype "input"))
    )
    (net (code "78") (name "VSS_SKC") (class "Default")
      (node (ref "C11") (pin "2") (pinfunction "2_2") (pintype "passive"))
      (node (ref "C12") (pin "2") (pinfunction "2_2") (pintype "passive"))
      (node (ref "C13") (pin "2") (pinfunction "2_2") (pintype "passive"))
      (node (ref "C14") (pin "2") (pinfunction "2_2") (pintype "passive"))
      (node (ref "C15") (pin "2") (pinfunction "2_2") (pintype "passive"))
      (node (ref "C16") (pin "1") (pinfunction "1_1") (pintype "passive"))
      (node (ref "C17") (pin "1") (pinfunction "1_1") (pintype "passive"))
      (node (ref "C18") (pin "1") (pinfunction "1_1") (pintype "passive"))
      (node (ref "C19") (pin "1") (pinfunction "1_1") (pintype "passive"))
      (node (ref "C20") (pin "2") (pinfunction "2_2") (pintype "passive"))
      (node (ref "C21") (pin "2") (pinfunction "2_2") (pintype "passive"))
      (node (ref "C22") (pin "2") (pinfunction "2_2") (pintype "passive"))
      (node (ref "C23") (pin "2") (pinfunction "2_2") (pintype "passive"))
      (node (ref "C24") (pin "2") (pinfunction "2_2") (pintype "passive"))
      (node (ref "C25") (pin "1") (pinfunction "1_1") (pintype "passive"))
      (node (ref "C26") (pin "1") (pinfunction "1_1") (pintype "passive"))
      (node (ref "C27") (pin "1") (pinfunction "1_1") (pintype "passive"))
      (node (ref "C28") (pin "1") (pinfunction "1_1") (pintype "passive"))
      (node (ref "C29") (pin "2") (pinfunction "2_2") (pintype "passive"))
      (node (ref "C30") (pin "2") (pinfunction "2_2") (pintype "passive"))
      (node (ref "C31") (pin "2") (pinfunction "2_2") (pintype "passive"))
      (node (ref "C32") (pin "2") (pinfunction "2_2") (pintype "passive"))
      (node (ref "C33") (pin "2") (pinfunction "2_2") (pintype "passive"))
      (node (ref "C34") (pin "1") (pinfunction "1_1") (pintype "passive"))
      (node (ref "C35") (pin "1") (pinfunction "1_1") (pintype "passive"))
      (node (ref "C36") (pin "1") (pinfunction "1_1") (pintype "passive"))
      (node (ref "C37") (pin "1") (pinfunction "1_1") (pintype "passive"))
      (node (ref "C38") (pin "2") (pinfunction "2_2") (pintype "passive"))
      (node (ref "C39") (pin "2") (pinfunction "2_2") (pintype "passive"))
      (node (ref "C40") (pin "2") (pinfunction "2_2") (pintype "passive"))
      (node (ref "C41") (pin "2") (pinfunction "2_2") (pintype "passive"))
      (node (ref "C42") (pin "2") (pinfunction "2_2") (pintype "passive"))
      (node (ref "C43") (pin "1") (pinfunction "1_1") (pintype "passive"))
      (node (ref "C44") (pin "1") (pinfunction "1_1") (pintype "passive"))
      (node (ref "C45") (pin "1") (pinfunction "1_1") (pintype "passive"))
      (node (ref "C46") (pin "1") (pinfunction "1_1") (pintype "passive"))
      (node (ref "P4") (pin "1") (pinfunction "1_1") (pintype "passive"))
      (node (ref "P4") (pin "11") (pinfunction "11_11") (pintype "passive"))
      (node (ref "P4") (pin "12") (pinfunction "12_12") (pintype "passive"))
      (node (ref "P4") (pin "2") (pinfunction "2_2") (pintype "passive"))
      (node (ref "P4") (pin "21") (pinfunction "21_21") (pintype "passive"))
      (node (ref "P4") (pin "22") (pinfunction "22_22") (pintype "passive"))
      (node (ref "P4") (pin "31") (pinfunction "31_31") (pintype "passive"))
      (node (ref "P4") (pin "32") (pinfunction "32_32") (pintype "passive"))
      (node (ref "U6") (pin "10") (pinfunction "GND_10") (pintype "power_in"))
      (node (ref "U7") (pin "10") (pinfunction "GND_10") (pintype "power_in"))
      (node (ref "U8") (pin "10") (pinfunction "GND_10") (pintype "power_in"))
      (node (ref "U9") (pin "10") (pinfunction "GND_10") (pintype "power_in"))
    )
  )
)
